# MP1584cir.net
KiCad netlist of a schematic drawn in EAGLE
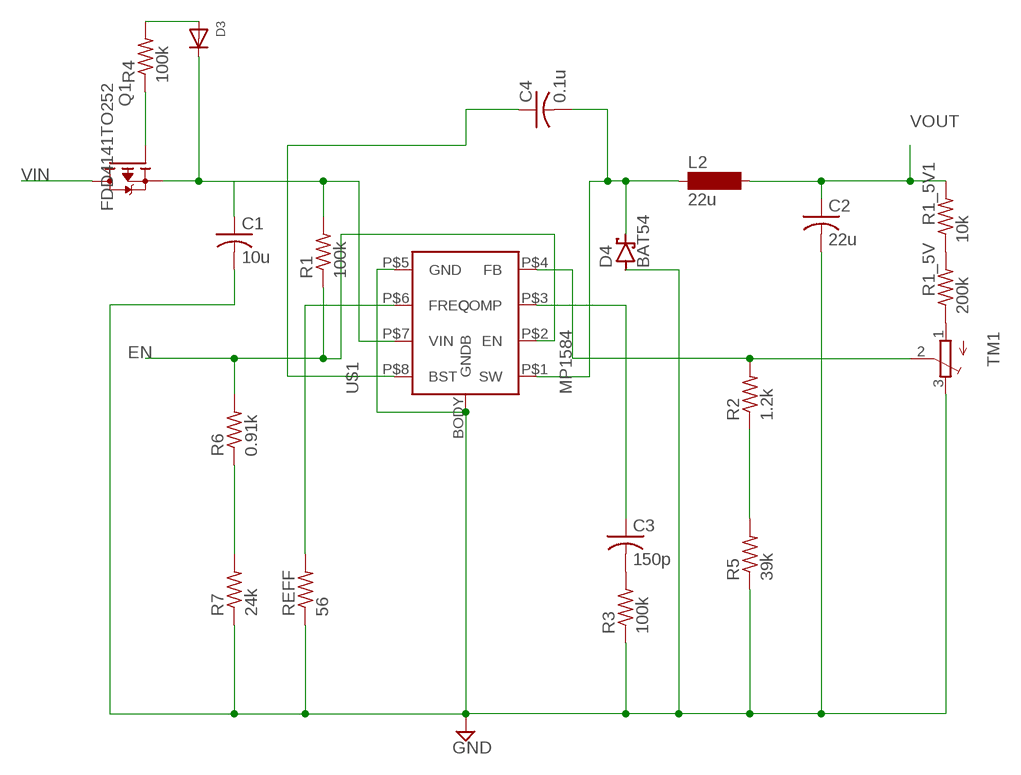
[diagram p0: schematic, sheet 1]

(export (version "E")
  (design (tool "Eeschema 10.0.6"))
  (components
    (comp (ref "C1")
      (value "10u")
      (footprint "eagle-import:C0805")
      (libsource (lib "eagle-import") (part "C-USC0805"))
    )
    (comp (ref "C2")
      (value "22u")
      (footprint "eagle-import:C0805")
      (libsource (lib "eagle-import") (part "C-USC0805"))
    )
    (comp (ref "C3")
      (value "150p")
      (footprint "eagle-import:C0805")
      (libsource (lib "eagle-import") (part "C-USC0805"))
    )
    (comp (ref "C4")
      (value "0.1u")
      (footprint "eagle-import:C0805")
      (libsource (lib "eagle-import") (part "C-USC0805"))
    )
    (comp (ref "D3")
      (value "DIODESOD-523")
      (footprint "eagle-import:SOD-523")
      (libsource (lib "eagle-import") (part "DIODESOD-523"))
    )
    (comp (ref "D4")
      (value "BAT54")
      (footprint "eagle-import:SOT23")
      (libsource (lib "eagle-import") (part "BAT54"))
    )
    (comp (ref "L2")
      (value "22u")
      (footprint "eagle-import:SM-NE45")
      (libsource (lib "eagle-import") (part "SM-NE45"))
    )
    (comp (ref "Q1")
      (value "FDD4141TO252")
      (footprint "eagle-import:TO252")
      (libsource (lib "eagle-import") (part "FDD4141TO252"))
    )
    (comp (ref "R1")
      (value "100k")
      (footprint "eagle-import:M0805")
      (libsource (lib "eagle-import") (part "R-US_M0805"))
    )
    (comp (ref "R1_5V")
      (value "200k")
      (footprint "eagle-import:M0805")
      (libsource (lib "eagle-import") (part "R-US_M0805"))
    )
    (comp (ref "R1_5V1")
      (value "10k")
      (footprint "eagle-import:M0805")
      (libsource (lib "eagle-import") (part "R-US_M0805"))
    )
    (comp (ref "R2")
      (value "1.2k")
      (footprint "eagle-import:M0805")
      (libsource (lib "eagle-import") (part "R-US_M0805"))
    )
    (comp (ref "R3")
      (value "100k")
      (footprint "eagle-import:M0805")
      (libsource (lib "eagle-import") (part "R-US_M0805"))
    )
    (comp (ref "R4")
      (value "100k")
      (footprint "eagle-import:M0805")
      (libsource (lib "eagle-import") (part "rcl_334_R-US_M0805"))
    )
    (comp (ref "R5")
      (value "39k")
      (footprint "eagle-import:M0805")
      (libsource (lib "eagle-import") (part "R-US_M0805"))
    )
    (comp (ref "R6")
      (value "0.91k")
      (footprint "eagle-import:M0805")
      (libsource (lib "eagle-import") (part "R-US_M0805"))
    )
    (comp (ref "R7")
      (value "24k")
      (footprint "eagle-import:M0805")
      (libsource (lib "eagle-import") (part "R-US_M0805"))
    )
    (comp (ref "REFF")
      (value "56")
      (footprint "eagle-import:M0805")
      (libsource (lib "eagle-import") (part "R-US_M0805"))
    )
    (comp (ref "TM1")
      (value "TRIMPOTTC33X")
      (footprint "eagle-import:TC33X")
      (libsource (lib "eagle-import") (part "TRIMPOTTC33X"))
    )
    (comp (ref "U$1")
      (value "MP1584")
      (footprint "eagle-import:MP")
      (libsource (lib "eagle-import") (part "MP1584"))
    )
  )
  (nets
    (net (code "1") (name "/EN") (class "Default")
      (node (ref "R1") (pin "1") (pinfunction "1_1") (pintype "passive"))
      (node (ref "R6") (pin "2") (pinfunction "2_2") (pintype "passive"))
      (node (ref "U$1") (pin "P$2") (pinfunction "EN_P$2") (pintype "bidirectional"))
    )
    (net (code "2") (name "/VIN") (class "Default")
      (node (ref "Q1") (pin "3") (pinfunction "D_3") (pintype "passive"))
    )
    (net (code "3") (name "/VOUT") (class "Default")
      (node (ref "C2") (pin "1") (pinfunction "1_1") (pintype "passive"))
      (node (ref "L2") (pin "2") (pinfunction "2_2") (pintype "passive"))
      (node (ref "R1_5V1") (pin "2") (pinfunction "2_2") (pintype "passive"))
    )
    (net (code "4") (name "GND") (class "Default")
      (node (ref "C1") (pin "2") (pinfunction "2_2") (pintype "passive"))
      (node (ref "C2") (pin "2") (pinfunction "2_2") (pintype "passive"))
      (node (ref "D4") (pin "1") (pinfunction "A_1") (pintype "passive"))
      (node (ref "R3") (pin "1") (pinfunction "1_1") (pintype "passive"))
      (node (ref "R5") (pin "1") (pinfunction "1_1") (pintype "passive"))
      (node (ref "R7") (pin "1") (pinfunction "1_1") (pintype "passive"))
      (node (ref "REFF") (pin "1") (pinfunction "1_1") (pintype "passive"))
      (node (ref "TM1") (pin "3") (pinfunction "E_3") (pintype "passive"))
      (node (ref "U$1") (pin "BODY") (pinfunction "GNDB_BODY") (pintype "bidirectional"))
      (node (ref "U$1") (pin "P$5") (pinfunction "GND_P$5") (pintype "bidirectional"))
    )
    (net (code "5") (name "Net-(C3-Pad2)") (class "Default")
      (node (ref "C3") (pin "2") (pinfunction "2_2") (pintype "passive"))
      (node (ref "R3") (pin "2") (pinfunction "2_2") (pintype "passive"))
    )
    (net (code "6") (name "Net-(D3-C)") (class "Default")
      (node (ref "C1") (pin "1") (pinfunction "1_1") (pintype "passive"))
      (node (ref "D3") (pin "K") (pinfunction "C_K") (pintype "passive"))
      (node (ref "Q1") (pin "2") (pinfunction "S_2") (pintype "passive"))
      (node (ref "R1") (pin "2") (pinfunction "2_2") (pintype "passive"))
      (node (ref "U$1") (pin "P$7") (pinfunction "VIN_P$7") (pintype "bidirectional"))
    )
    (net (code "7") (name "Net-(D3-PadA)") (class "Default")
      (node (ref "D3") (pin "A") (pinfunction "A_A") (pintype "passive"))
      (node (ref "R4") (pin "2") (pinfunction "2_2") (pintype "passive"))
    )
    (net (code "8") (name "Net-(D4-C)") (class "Default")
      (node (ref "C4") (pin "2") (pinfunction "2_2") (pintype "passive"))
      (node (ref "D4") (pin "3") (pinfunction "C_3") (pintype "passive"))
      (node (ref "L2") (pin "1") (pinfunction "1_1") (pintype "passive"))
      (node (ref "U$1") (pin "P$1") (pinfunction "SW_P$1") (pintype "bidirectional"))
    )
    (net (code "9") (name "Net-(Q1-G)") (class "Default")
      (node (ref "Q1") (pin "1") (pinfunction "G_1") (pintype "passive"))
      (node (ref "R4") (pin "1") (pinfunction "1_1") (pintype "passive"))
    )
    (net (code "10") (name "Net-(R1_5V-Pad2)") (class "Default")
      (node (ref "R1_5V") (pin "2") (pinfunction "2_2") (pintype "passive"))
      (node (ref "R1_5V1") (pin "1") (pinfunction "1_1") (pintype "passive"))
    )
    (net (code "11") (name "Net-(R2-Pad1)") (class "Default")
      (node (ref "R2") (pin "1") (pinfunction "1_1") (pintype "passive"))
      (node (ref "R5") (pin "2") (pinfunction "2_2") (pintype "passive"))
    )
    (net (code "12") (name "Net-(R6-Pad1)") (class "Default")
      (node (ref "R6") (pin "1") (pinfunction "1_1") (pintype "passive"))
      (node (ref "R7") (pin "2") (pinfunction "2_2") (pintype "passive"))
    )
    (net (code "13") (name "Net-(TM1-A)") (class "Default")
      (node (ref "R1_5V") (pin "1") (pinfunction "1_1") (pintype "passive"))
      (node (ref "TM1") (pin "1") (pinfunction "A_1") (pintype "passive"))
    )
    (net (code "14") (name "Net-(TM1-S)") (class "Default")
      (node (ref "R2") (pin "2") (pinfunction "2_2") (pintype "passive"))
      (node (ref "TM1") (pin "2") (pinfunction "S_2") (pintype "passive"))
      (node (ref "U$1") (pin "P$4") (pinfunction "FB_P$4") (pintype "bidirectional"))
    )
    (net (code "15") (name "Net-(U$1-BST)") (class "Default")
      (node (ref "C4") (pin "1") (pinfunction "1_1") (pintype "passive"))
      (node (ref "U$1") (pin "P$8") (pinfunction "BST_P$8") (pintype "bidirectional"))
    )
    (net (code "16") (name "Net-(U$1-COMP)") (class "Default")
      (node (ref "C3") (pin "1") (pinfunction "1_1") (pintype "passive"))
      (node (ref "U$1") (pin "P$3") (pinfunction "COMP_P$3") (pintype "bidirectional"))
    )
    (net (code "17") (name "Net-(U$1-FREQ)") (class "Default")
      (node (ref "REFF") (pin "2") (pinfunction "2_2") (pintype "passive"))
      (node (ref "U$1") (pin "P$6") (pinfunction "FREQ_P$6") (pintype "bidirectional"))
    )
  )
)
